# OUT_RELE.net
KiCad netlist of a schematic drawn in Altium Designer
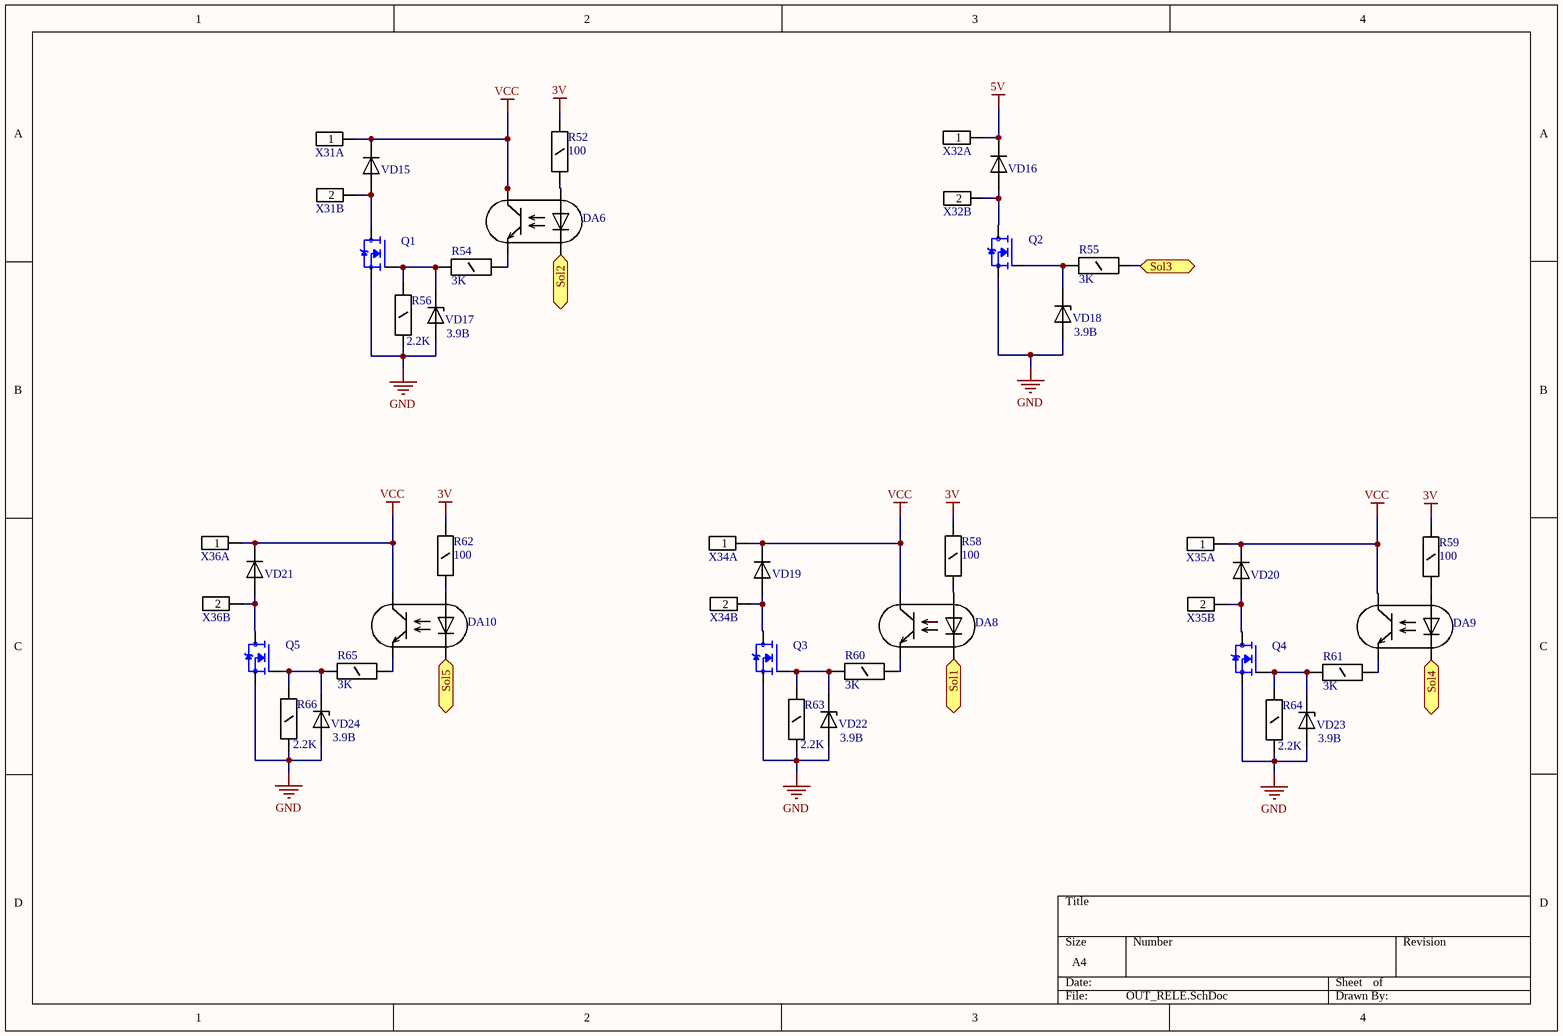
[diagram p0: OUT_RELE.SchDoc]

(export (version "E")
  (design (tool "Eeschema 10.0.6"))
  (components
    (comp (ref "DA6")
      (value "PC817")
      (footprint "SOIC254P1000X400-4N")
      (description "оптрон, SMD")
      (libsource (lib "LEDendIND") (part "KPC357NT"))
    )
    (comp (ref "DA8")
      (value "PC817")
      (footprint "SOIC254P1000X400-4N")
      (description "оптрон, SMD")
      (libsource (lib "LEDendIND") (part "KPC357NT"))
    )
    (comp (ref "DA9")
      (value "PC817")
      (footprint "SOIC254P1000X400-4N")
      (description "оптрон, SMD")
      (libsource (lib "LEDendIND") (part "KPC357NT"))
    )
    (comp (ref "DA10")
      (value "PC817")
      (footprint "SOIC254P1000X400-4N")
      (description "оптрон, SMD")
      (libsource (lib "LEDendIND") (part "KPC357NT"))
    )
    (comp (ref "Q1")
      (value "IRFZ44N")
      (footprint "DPAK254P1524X483-3N:DPAK254P1524X483-3N")
      (description "N-Channel 55V 49A (Tc) 3.8W (Ta), 94W (Tc) Surface Mount D2PAK")
      (fields (field (name "MP") "IRFZ44NSTRRPBF") (field (name "MF") "Infineon Technologies"))
      (libsource (lib "Diod_transistor") (part "IRFZ44NSTRRPBF"))
    )
    (comp (ref "Q2")
      (value "IRFZ44N")
      (footprint "DPAK254P1524X483-3N:DPAK254P1524X483-3N")
      (description "N-Channel 55V 49A (Tc) 3.8W (Ta), 94W (Tc) Surface Mount D2PAK")
      (fields (field (name "MP") "IRFZ44NSTRRPBF") (field (name "MF") "Infineon Technologies"))
      (libsource (lib "Diod_transistor") (part "IRFZ44NSTRRPBF"))
    )
    (comp (ref "Q3")
      (value "IRFZ44N")
      (footprint "DPAK254P1524X483-3N:DPAK254P1524X483-3N")
      (description "N-Channel 55V 49A (Tc) 3.8W (Ta), 94W (Tc) Surface Mount D2PAK")
      (fields (field (name "MP") "IRFZ44NSTRRPBF") (field (name "MF") "Infineon Technologies"))
      (libsource (lib "Diod_transistor") (part "IRFZ44NSTRRPBF"))
    )
    (comp (ref "Q4")
      (value "IRFZ44N")
      (footprint "DPAK254P1524X483-3N:DPAK254P1524X483-3N")
      (description "N-Channel 55V 49A (Tc) 3.8W (Ta), 94W (Tc) Surface Mount D2PAK")
      (fields (field (name "MP") "IRFZ44NSTRRPBF") (field (name "MF") "Infineon Technologies"))
      (libsource (lib "Diod_transistor") (part "IRFZ44NSTRRPBF"))
    )
    (comp (ref "Q5")
      (value "IRFZ44N")
      (footprint "DPAK254P1524X483-3N:DPAK254P1524X483-3N")
      (description "N-Channel 55V 49A (Tc) 3.8W (Ta), 94W (Tc) Surface Mount D2PAK")
      (fields (field (name "MP") "IRFZ44NSTRRPBF") (field (name "MF") "Infineon Technologies"))
      (libsource (lib "Diod_transistor") (part "IRFZ44NSTRRPBF"))
    )
    (comp (ref "R52")
      (value "100")
      (footprint "R_1206")
      (description "0,25 Вт")
      (fields (field (name "POWER") "0.25 Вт") (field (name "TOLERANCE") "5%"))
      (libsource (lib "") (part "Резистор 1206_2"))
    )
    (comp (ref "R54")
      (value "3K")
      (footprint "R_1206")
      (description "0,25 Вт")
      (fields (field (name "POWER") "0.25 Вт") (field (name "TOLERANCE") "5%"))
      (libsource (lib "") (part "Резистор 1206_1"))
    )
    (comp (ref "R55")
      (value "3K")
      (footprint "R_1206")
      (description "0,25 Вт")
      (fields (field (name "POWER") "0.25 Вт") (field (name "TOLERANCE") "5%"))
      (libsource (lib "") (part "Резистор 1206_1"))
    )
    (comp (ref "R56")
      (value "2.2K")
      (footprint "R_1206")
      (description "0,25 Вт")
      (fields (field (name "POWER") "0.25 Вт") (field (name "TOLERANCE") "5%"))
      (libsource (lib "Res_end_Cap") (part "Резистор 1206"))
    )
    (comp (ref "R58")
      (value "100")
      (footprint "R_1206")
      (description "0,25 Вт")
      (fields (field (name "POWER") "0.25 Вт") (field (name "TOLERANCE") "5%"))
      (libsource (lib "") (part "Резистор 1206_2"))
    )
    (comp (ref "R59")
      (value "100")
      (footprint "R_1206")
      (description "0,25 Вт")
      (fields (field (name "POWER") "0.25 Вт") (field (name "TOLERANCE") "5%"))
      (libsource (lib "") (part "Резистор 1206_2"))
    )
    (comp (ref "R60")
      (value "3K")
      (footprint "R_1206")
      (description "0,25 Вт")
      (fields (field (name "POWER") "0.25 Вт") (field (name "TOLERANCE") "5%"))
      (libsource (lib "") (part "Резистор 1206_1"))
    )
    (comp (ref "R61")
      (value "3K")
      (footprint "R_1206")
      (description "0,25 Вт")
      (fields (field (name "POWER") "0.25 Вт") (field (name "TOLERANCE") "5%"))
      (libsource (lib "") (part "Резистор 1206_1"))
    )
    (comp (ref "R62")
      (value "100")
      (footprint "R_1206")
      (description "0,25 Вт")
      (fields (field (name "POWER") "0.25 Вт") (field (name "TOLERANCE") "5%"))
      (libsource (lib "") (part "Резистор 1206_2"))
    )
    (comp (ref "R63")
      (value "2.2K")
      (footprint "R_1206")
      (description "0,25 Вт")
      (fields (field (name "POWER") "0.25 Вт") (field (name "TOLERANCE") "5%"))
      (libsource (lib "Res_end_Cap") (part "Резистор 1206"))
    )
    (comp (ref "R64")
      (value "2.2K")
      (footprint "R_1206")
      (description "0,25 Вт")
      (fields (field (name "POWER") "0.25 Вт") (field (name "TOLERANCE") "5%"))
      (libsource (lib "Res_end_Cap") (part "Резистор 1206"))
    )
    (comp (ref "R65")
      (value "3K")
      (footprint "R_1206")
      (description "0,25 Вт")
      (fields (field (name "POWER") "0.25 Вт") (field (name "TOLERANCE") "5%"))
      (libsource (lib "") (part "Резистор 1206_1"))
    )
    (comp (ref "R66")
      (value "2.2K")
      (footprint "R_1206")
      (description "0,25 Вт")
      (fields (field (name "POWER") "0.25 Вт") (field (name "TOLERANCE") "5%"))
      (libsource (lib "Res_end_Cap") (part "Резистор 1206"))
    )
    (comp (ref "VD15")
      (value "SMA4007")
      (footprint "SMA (DO-214AC)")
      (description "диод, SMD")
      (libsource (lib "Диоды и транзисторы") (part "SMA400*"))
    )
    (comp (ref "VD16")
      (value "SMA4007")
      (footprint "SMA (DO-214AC)")
      (description "диод, SMD")
      (libsource (lib "Диоды и транзисторы") (part "SMA400*"))
    )
    (comp (ref "VD17")
      (value "3.9В")
      (footprint "DL-35")
      (description "стабилитрон, SMD")
      (fields (field (name "POWER") "0.5 Вт"))
      (libsource (lib "Diod_transistor") (part "BZV55C***"))
    )
    (comp (ref "VD18")
      (value "3.9В")
      (footprint "DL-35")
      (description "стабилитрон, SMD")
      (fields (field (name "POWER") "0.5 Вт"))
      (libsource (lib "Diod_transistor") (part "BZV55C***"))
    )
    (comp (ref "VD19")
      (value "SMA4007")
      (footprint "SMA (DO-214AC)")
      (description "диод, SMD")
      (libsource (lib "Диоды и транзисторы") (part "SMA400*"))
    )
    (comp (ref "VD20")
      (value "SMA4007")
      (footprint "SMA (DO-214AC)")
      (description "диод, SMD")
      (libsource (lib "Диоды и транзисторы") (part "SMA400*"))
    )
    (comp (ref "VD21")
      (value "SMA4007")
      (footprint "SMA (DO-214AC)")
      (description "диод, SMD")
      (libsource (lib "Диоды и транзисторы") (part "SMA400*"))
    )
    (comp (ref "VD22")
      (value "3.9В")
      (footprint "DL-35")
      (description "стабилитрон, SMD")
      (fields (field (name "POWER") "0.5 Вт"))
      (libsource (lib "Diod_transistor") (part "BZV55C***"))
    )
    (comp (ref "VD23")
      (value "3.9В")
      (footprint "DL-35")
      (description "стабилитрон, SMD")
      (fields (field (name "POWER") "0.5 Вт"))
      (libsource (lib "Diod_transistor") (part "BZV55C***"))
    )
    (comp (ref "VD24")
      (value "3.9В")
      (footprint "DL-35")
      (description "стабилитрон, SMD")
      (fields (field (name "POWER") "0.5 Вт"))
      (libsource (lib "Diod_transistor") (part "BZV55C***"))
    )
    (comp (ref "X31")
      (value "DG508V-02")
      (footprint "DG508V-02")
      (description "клеммник винтовой 2к.,5.08мм")
      (libsource (lib "Klemniki") (part "DG508V-02"))
    )
    (comp (ref "X32")
      (value "DG508V-02")
      (footprint "DG508V-02")
      (description "клеммник винтовой 2к.,5.08мм")
      (libsource (lib "Klemniki") (part "DG508V-02"))
    )
    (comp (ref "X34")
      (value "DG508V-02")
      (footprint "DG508V-02")
      (description "клеммник винтовой 2к.,5.08мм")
      (libsource (lib "Klemniki") (part "DG508V-02"))
    )
    (comp (ref "X35")
      (value "DG508V-02")
      (footprint "DG508V-02")
      (description "клеммник винтовой 2к.,5.08мм")
      (libsource (lib "Klemniki") (part "DG508V-02"))
    )
    (comp (ref "X36")
      (value "DG508V-02")
      (footprint "DG508V-02")
      (description "клеммник винтовой 2к.,5.08мм")
      (libsource (lib "Klemniki") (part "DG508V-02"))
    )
  )
  (nets
    (net (code "1") (name "/Sol1") (class "Default")
      (node (ref "DA8") (pin "2") (pinfunction "2_2") (pintype "passive"))
    )
    (net (code "2") (name "/Sol2") (class "Default")
      (node (ref "DA6") (pin "2") (pinfunction "2_2") (pintype "passive"))
    )
    (net (code "3") (name "/Sol3") (class "Default")
      (node (ref "R55") (pin "2") (pinfunction "2_2") (pintype "passive"))
    )
    (net (code "4") (name "/Sol4") (class "Default")
      (node (ref "DA9") (pin "2") (pinfunction "2_2") (pintype "passive"))
    )
    (net (code "5") (name "/Sol5") (class "Default")
      (node (ref "DA10") (pin "2") (pinfunction "2_2") (pintype "passive"))
    )
    (net (code "6") (name "3V") (class "Default")
      (node (ref "R52") (pin "1") (pinfunction "1_1") (pintype "passive"))
      (node (ref "R58") (pin "1") (pinfunction "1_1") (pintype "passive"))
      (node (ref "R59") (pin "1") (pinfunction "1_1") (pintype "passive"))
      (node (ref "R62") (pin "1") (pinfunction "1_1") (pintype "passive"))
    )
    (net (code "7") (name "5V") (class "Default")
      (node (ref "VD16") (pin "K") (pinfunction "K_K") (pintype "passive"))
      (node (ref "X32") (pin "1") (pinfunction "1_1") (pintype "passive"))
    )
    (net (code "8") (name "GND") (class "Default")
      (node (ref "Q1") (pin "3") (pinfunction "S_3") (pintype "passive"))
      (node (ref "Q2") (pin "3") (pinfunction "S_3") (pintype "passive"))
      (node (ref "Q3") (pin "3") (pinfunction "S_3") (pintype "passive"))
      (node (ref "Q4") (pin "3") (pinfunction "S_3") (pintype "passive"))
      (node (ref "Q5") (pin "3") (pinfunction "S_3") (pintype "passive"))
      (node (ref "R56") (pin "1") (pinfunction "1_1") (pintype "passive"))
      (node (ref "R63") (pin "1") (pinfunction "1_1") (pintype "passive"))
      (node (ref "R64") (pin "1") (pinfunction "1_1") (pintype "passive"))
      (node (ref "R66") (pin "1") (pinfunction "1_1") (pintype "passive"))
      (node (ref "VD17") (pin "1") (pinfunction "1_1") (pintype "passive"))
      (node (ref "VD18") (pin "1") (pinfunction "1_1") (pintype "passive"))
      (node (ref "VD22") (pin "1") (pinfunction "1_1") (pintype "passive"))
      (node (ref "VD23") (pin "1") (pinfunction "1_1") (pintype "passive"))
      (node (ref "VD24") (pin "1") (pinfunction "1_1") (pintype "passive"))
    )
    (net (code "9") (name "Net-(DA6-Pad1)") (class "Default")
      (node (ref "DA6") (pin "1") (pinfunction "1_1") (pintype "passive"))
      (node (ref "R52") (pin "2") (pinfunction "2_2") (pintype "passive"))
    )
    (net (code "10") (name "Net-(DA6-Pad3)") (class "Default")
      (node (ref "DA6") (pin "3") (pinfunction "3_3") (pintype "passive"))
      (node (ref "R54") (pin "2") (pinfunction "2_2") (pintype "passive"))
    )
    (net (code "11") (name "Net-(DA8-Pad1)") (class "Default")
      (node (ref "DA8") (pin "1") (pinfunction "1_1") (pintype "passive"))
      (node (ref "R58") (pin "2") (pinfunction "2_2") (pintype "passive"))
    )
    (net (code "12") (name "Net-(DA8-Pad3)") (class "Default")
      (node (ref "DA8") (pin "3") (pinfunction "3_3") (pintype "passive"))
      (node (ref "R60") (pin "2") (pinfunction "2_2") (pintype "passive"))
    )
    (net (code "13") (name "Net-(DA9-Pad1)") (class "Default")
      (node (ref "DA9") (pin "1") (pinfunction "1_1") (pintype "passive"))
      (node (ref "R59") (pin "2") (pinfunction "2_2") (pintype "passive"))
    )
    (net (code "14") (name "Net-(DA9-Pad3)") (class "Default")
      (node (ref "DA9") (pin "3") (pinfunction "3_3") (pintype "passive"))
      (node (ref "R61") (pin "2") (pinfunction "2_2") (pintype "passive"))
    )
    (net (code "15") (name "Net-(DA10-Pad1)") (class "Default")
      (node (ref "DA10") (pin "1") (pinfunction "1_1") (pintype "passive"))
      (node (ref "R62") (pin "2") (pinfunction "2_2") (pintype "passive"))
    )
    (net (code "16") (name "Net-(DA10-Pad3)") (class "Default")
      (node (ref "DA10") (pin "3") (pinfunction "3_3") (pintype "passive"))
      (node (ref "R65") (pin "2") (pinfunction "2_2") (pintype "passive"))
    )
    (net (code "17") (name "Net-(Q1-D)") (class "Default")
      (node (ref "Q1") (pin "2") (pinfunction "D_2") (pintype "passive"))
      (node (ref "VD15") (pin "A") (pinfunction "A_A") (pintype "passive"))
      (node (ref "X31") (pin "2") (pinfunction "2_2") (pintype "passive"))
    )
    (net (code "18") (name "Net-(Q1-G)") (class "Default")
      (node (ref "Q1") (pin "1") (pinfunction "G_1") (pintype "passive"))
      (node (ref "R54") (pin "1") (pinfunction "1_1") (pintype "passive"))
      (node (ref "R56") (pin "2") (pinfunction "2_2") (pintype "passive"))
      (node (ref "VD17") (pin "2") (pinfunction "2_2") (pintype "passive"))
    )
    (net (code "19") (name "Net-(Q2-D)") (class "Default")
      (node (ref "Q2") (pin "2") (pinfunction "D_2") (pintype "passive"))
      (node (ref "VD16") (pin "A") (pinfunction "A_A") (pintype "passive"))
      (node (ref "X32") (pin "2") (pinfunction "2_2") (pintype "passive"))
    )
    (net (code "20") (name "Net-(Q2-G)") (class "Default")
      (node (ref "Q2") (pin "1") (pinfunction "G_1") (pintype "passive"))
      (node (ref "R55") (pin "1") (pinfunction "1_1") (pintype "passive"))
      (node (ref "VD18") (pin "2") (pinfunction "2_2") (pintype "passive"))
    )
    (net (code "21") (name "Net-(Q3-D)") (class "Default")
      (node (ref "Q3") (pin "2") (pinfunction "D_2") (pintype "passive"))
      (node (ref "VD19") (pin "A") (pinfunction "A_A") (pintype "passive"))
      (node (ref "X34") (pin "2") (pinfunction "2_2") (pintype "passive"))
    )
    (net (code "22") (name "Net-(Q3-G)") (class "Default")
      (node (ref "Q3") (pin "1") (pinfunction "G_1") (pintype "passive"))
      (node (ref "R60") (pin "1") (pinfunction "1_1") (pintype "passive"))
      (node (ref "R63") (pin "2") (pinfunction "2_2") (pintype "passive"))
      (node (ref "VD22") (pin "2") (pinfunction "2_2") (pintype "passive"))
    )
    (net (code "23") (name "Net-(Q4-D)") (class "Default")
      (node (ref "Q4") (pin "2") (pinfunction "D_2") (pintype "passive"))
      (node (ref "VD20") (pin "A") (pinfunction "A_A") (pintype "passive"))
      (node (ref "X35") (pin "2") (pinfunction "2_2") (pintype "passive"))
    )
    (net (code "24") (name "Net-(Q4-G)") (class "Default")
      (node (ref "Q4") (pin "1") (pinfunction "G_1") (pintype "passive"))
      (node (ref "R61") (pin "1") (pinfunction "1_1") (pintype "passive"))
      (node (ref "R64") (pin "2") (pinfunction "2_2") (pintype "passive"))
      (node (ref "VD23") (pin "2") (pinfunction "2_2") (pintype "passive"))
    )
    (net (code "25") (name "Net-(Q5-D)") (class "Default")
      (node (ref "Q5") (pin "2") (pinfunction "D_2") (pintype "passive"))
      (node (ref "VD21") (pin "A") (pinfunction "A_A") (pintype "passive"))
      (node (ref "X36") (pin "2") (pinfunction "2_2") (pintype "passive"))
    )
    (net (code "26") (name "Net-(Q5-G)") (class "Default")
      (node (ref "Q5") (pin "1") (pinfunction "G_1") (pintype "passive"))
      (node (ref "R65") (pin "1") (pinfunction "1_1") (pintype "passive"))
      (node (ref "R66") (pin "2") (pinfunction "2_2") (pintype "passive"))
      (node (ref "VD24") (pin "2") (pinfunction "2_2") (pintype "passive"))
    )
    (net (code "27") (name "VCC") (class "Default")
      (node (ref "DA10") (pin "4") (pinfunction "4_4") (pintype "passive"))
      (node (ref "DA6") (pin "4") (pinfunction "4_4") (pintype "passive"))
      (node (ref "DA8") (pin "4") (pinfunction "4_4") (pintype "passive"))
      (node (ref "DA9") (pin "4") (pinfunction "4_4") (pintype "passive"))
      (node (ref "VD15") (pin "K") (pinfunction "K_K") (pintype "passive"))
      (node (ref "VD19") (pin "K") (pinfunction "K_K") (pintype "passive"))
      (node (ref "VD20") (pin "K") (pinfunction "K_K") (pintype "passive"))
      (node (ref "VD21") (pin "K") (pinfunction "K_K") (pintype "passive"))
      (node (ref "X31") (pin "1") (pinfunction "1_1") (pintype "passive"))
      (node (ref "X34") (pin "1") (pinfunction "1_1") (pintype "passive"))
      (node (ref "X35") (pin "1") (pinfunction "1_1") (pintype "passive"))
      (node (ref "X36") (pin "1") (pinfunction "1_1") (pintype "passive"))
    )
  )
)
